# Adapter-TenX-Resistors.net
KiCad netlist of a schematic drawn in EAGLE
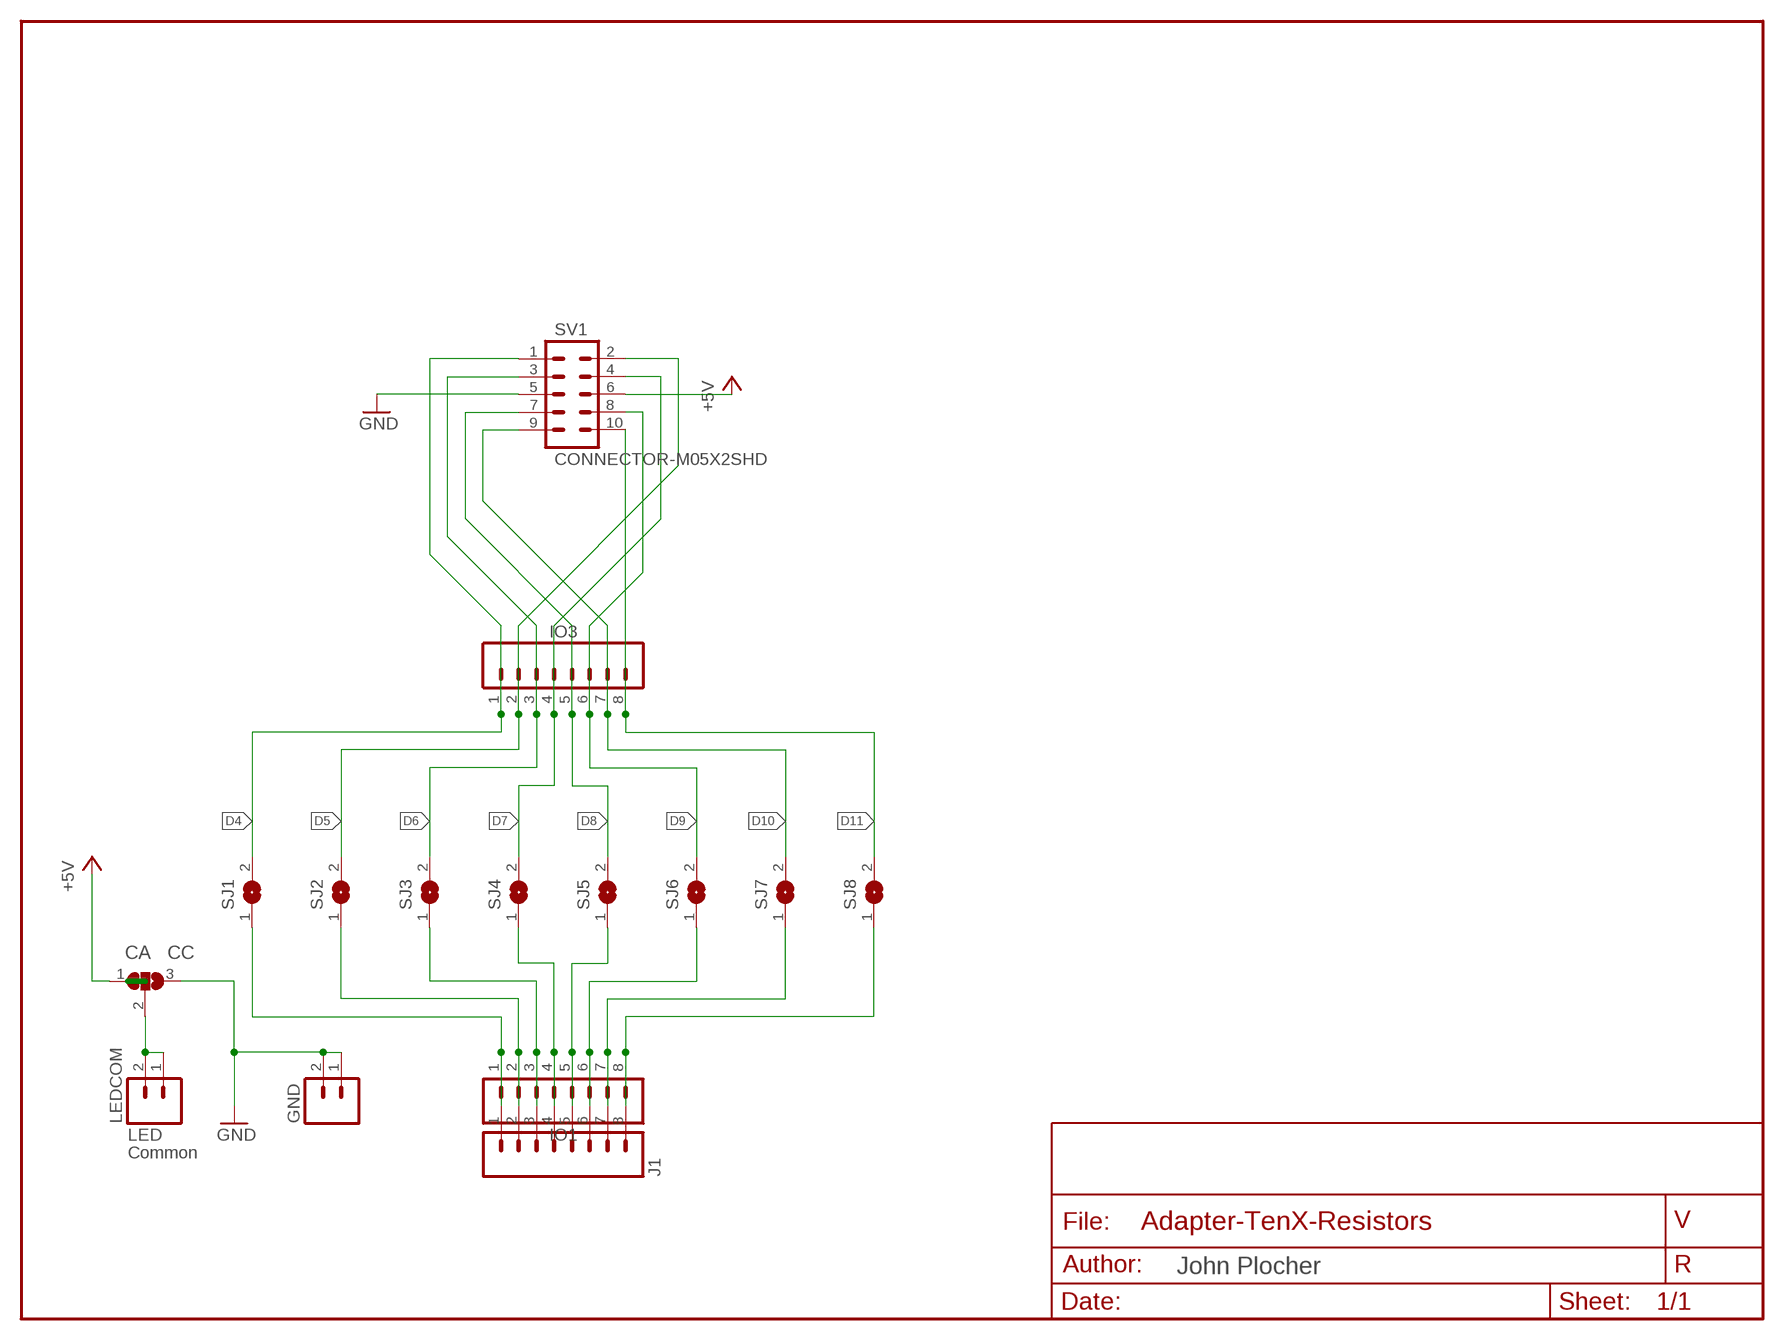
[diagram p0: schematic, sheet 1]

(export (version "E")
  (design (tool "Eeschema 10.0.6"))
  (components
    (comp (ref "GND")
      (value "M02POLAR_LOCK")
      (footprint "eagle-import:MOLEX-1X2_LOCK")
      (libsource (lib "eagle-import") (part "M02POLAR_LOCK"))
    )
    (comp (ref "IO1")
      (value "M081X08")
      (footprint "eagle-import:1X08")
      (libsource (lib "eagle-import") (part "M081X08"))
    )
    (comp (ref "IO3")
      (value "M081X08")
      (footprint "eagle-import:1X08")
      (libsource (lib "eagle-import") (part "M081X08"))
    )
    (comp (ref "J1")
      (value "CONNECTOR-M08LOCK_LONGPADS")
      (footprint "eagle-import:1X08_LOCK_LONGPADS")
      (libsource (lib "eagle-import") (part "CONNECTOR-M08LOCK_LONGPADS"))
    )
    (comp (ref "LEDCOM")
      (value "M02POLAR_LOCK")
      (footprint "eagle-import:MOLEX-1X2_LOCK")
      (libsource (lib "eagle-import") (part "M02POLAR_LOCK"))
    )
    (comp (ref "P1")
      (value "CA CC")
      (footprint "eagle-import:3P-SMD-2X4.8")
      (libsource (lib "eagle-import") (part "PAD-SOLDERJUMPER-2WAYT"))
    )
    (comp (ref "SJ1") (value "SJ") (footprint "eagle-import:SJ") (libsource (lib "eagle-import") (part "SJ")))
    (comp (ref "SJ2") (value "SJ") (footprint "eagle-import:SJ") (libsource (lib "eagle-import") (part "SJ")))
    (comp (ref "SJ3") (value "SJ") (footprint "eagle-import:SJ") (libsource (lib "eagle-import") (part "SJ")))
    (comp (ref "SJ4") (value "SJ") (footprint "eagle-import:SJ") (libsource (lib "eagle-import") (part "SJ")))
    (comp (ref "SJ5") (value "SJ") (footprint "eagle-import:SJ") (libsource (lib "eagle-import") (part "SJ")))
    (comp (ref "SJ6") (value "SJ") (footprint "eagle-import:SJ") (libsource (lib "eagle-import") (part "SJ")))
    (comp (ref "SJ7") (value "SJ") (footprint "eagle-import:SJ") (libsource (lib "eagle-import") (part "SJ")))
    (comp (ref "SJ8") (value "SJ") (footprint "eagle-import:SJ") (libsource (lib "eagle-import") (part "SJ")))
    (comp (ref "SV1")
      (value "CONNECTOR-M05X2SHD")
      (footprint "eagle-import:2X5-SHROUDED")
      (libsource (lib "eagle-import") (part "CONNECTOR-M05X2SHD"))
    )
  )
  (nets
    (net (code "1") (name "+5V") (class "Default")
      (node (ref "P1") (pin "1") (pinfunction "1_1") (pintype "passive"))
      (node (ref "SV1") (pin "6") (pinfunction "6_6") (pintype "passive"))
    )
    (net (code "2") (name "D4") (class "Default")
      (node (ref "IO3") (pin "1") (pinfunction "1_1") (pintype "passive"))
      (node (ref "SJ1") (pin "2") (pinfunction "2_2") (pintype "passive"))
      (node (ref "SV1") (pin "1") (pinfunction "1_1") (pintype "passive"))
    )
    (net (code "3") (name "D5") (class "Default")
      (node (ref "IO3") (pin "2") (pinfunction "2_2") (pintype "passive"))
      (node (ref "SJ2") (pin "2") (pinfunction "2_2") (pintype "passive"))
      (node (ref "SV1") (pin "2") (pinfunction "2_2") (pintype "passive"))
    )
    (net (code "4") (name "D6") (class "Default")
      (node (ref "IO3") (pin "3") (pinfunction "3_3") (pintype "passive"))
      (node (ref "SJ3") (pin "2") (pinfunction "2_2") (pintype "passive"))
      (node (ref "SV1") (pin "3") (pinfunction "3_3") (pintype "passive"))
    )
    (net (code "5") (name "D7") (class "Default")
      (node (ref "IO3") (pin "4") (pinfunction "4_4") (pintype "passive"))
      (node (ref "SJ4") (pin "2") (pinfunction "2_2") (pintype "passive"))
      (node (ref "SV1") (pin "4") (pinfunction "4_4") (pintype "passive"))
    )
    (net (code "6") (name "D8") (class "Default")
      (node (ref "IO3") (pin "5") (pinfunction "5_5") (pintype "passive"))
      (node (ref "SJ5") (pin "2") (pinfunction "2_2") (pintype "passive"))
      (node (ref "SV1") (pin "7") (pinfunction "7_7") (pintype "passive"))
    )
    (net (code "7") (name "D9") (class "Default")
      (node (ref "IO3") (pin "6") (pinfunction "6_6") (pintype "passive"))
      (node (ref "SJ6") (pin "2") (pinfunction "2_2") (pintype "passive"))
      (node (ref "SV1") (pin "8") (pinfunction "8_8") (pintype "passive"))
    )
    (net (code "8") (name "D10") (class "Default")
      (node (ref "IO3") (pin "7") (pinfunction "7_7") (pintype "passive"))
      (node (ref "SJ7") (pin "2") (pinfunction "2_2") (pintype "passive"))
      (node (ref "SV1") (pin "9") (pinfunction "9_9") (pintype "passive"))
    )
    (net (code "9") (name "D11") (class "Default")
      (node (ref "IO3") (pin "8") (pinfunction "8_8") (pintype "passive"))
      (node (ref "SJ8") (pin "2") (pinfunction "2_2") (pintype "passive"))
      (node (ref "SV1") (pin "10") (pinfunction "10_10") (pintype "passive"))
    )
    (net (code "10") (name "GND") (class "Default")
      (node (ref "GND") (pin "1") (pinfunction "1_1") (pintype "passive"))
      (node (ref "GND") (pin "2") (pinfunction "2_2") (pintype "passive"))
      (node (ref "P1") (pin "3") (pinfunction "3_3") (pintype "passive"))
      (node (ref "SV1") (pin "5") (pinfunction "5_5") (pintype "passive"))
    )
    (net (code "11") (name "Net-(IO1-Pad1)") (class "Default")
      (node (ref "IO1") (pin "1") (pinfunction "1_1") (pintype "passive"))
      (node (ref "J1") (pin "1") (pinfunction "1_1") (pintype "passive"))
      (node (ref "SJ1") (pin "1") (pinfunction "1_1") (pintype "passive"))
    )
    (net (code "12") (name "Net-(IO1-Pad2)") (class "Default")
      (node (ref "IO1") (pin "2") (pinfunction "2_2") (pintype "passive"))
      (node (ref "J1") (pin "2") (pinfunction "2_2") (pintype "passive"))
      (node (ref "SJ2") (pin "1") (pinfunction "1_1") (pintype "passive"))
    )
    (net (code "13") (name "Net-(IO1-Pad3)") (class "Default")
      (node (ref "IO1") (pin "3") (pinfunction "3_3") (pintype "passive"))
      (node (ref "J1") (pin "3") (pinfunction "3_3") (pintype "passive"))
      (node (ref "SJ3") (pin "1") (pinfunction "1_1") (pintype "passive"))
    )
    (net (code "14") (name "Net-(IO1-Pad4)") (class "Default")
      (node (ref "IO1") (pin "4") (pinfunction "4_4") (pintype "passive"))
      (node (ref "J1") (pin "4") (pinfunction "4_4") (pintype "passive"))
      (node (ref "SJ4") (pin "1") (pinfunction "1_1") (pintype "passive"))
    )
    (net (code "15") (name "Net-(IO1-Pad5)") (class "Default")
      (node (ref "IO1") (pin "5") (pinfunction "5_5") (pintype "passive"))
      (node (ref "J1") (pin "5") (pinfunction "5_5") (pintype "passive"))
      (node (ref "SJ5") (pin "1") (pinfunction "1_1") (pintype "passive"))
    )
    (net (code "16") (name "Net-(IO1-Pad6)") (class "Default")
      (node (ref "IO1") (pin "6") (pinfunction "6_6") (pintype "passive"))
      (node (ref "J1") (pin "6") (pinfunction "6_6") (pintype "passive"))
      (node (ref "SJ6") (pin "1") (pinfunction "1_1") (pintype "passive"))
    )
    (net (code "17") (name "Net-(IO1-Pad7)") (class "Default")
      (node (ref "IO1") (pin "7") (pinfunction "7_7") (pintype "passive"))
      (node (ref "J1") (pin "7") (pinfunction "7_7") (pintype "passive"))
      (node (ref "SJ7") (pin "1") (pinfunction "1_1") (pintype "passive"))
    )
    (net (code "18") (name "Net-(IO1-Pad8)") (class "Default")
      (node (ref "IO1") (pin "8") (pinfunction "8_8") (pintype "passive"))
      (node (ref "J1") (pin "8") (pinfunction "8_8") (pintype "passive"))
      (node (ref "SJ8") (pin "1") (pinfunction "1_1") (pintype "passive"))
    )
    (net (code "19") (name "Net-(LEDCOM-Pad1)") (class "Default")
      (node (ref "LEDCOM") (pin "1") (pinfunction "1_1") (pintype "passive"))
      (node (ref "LEDCOM") (pin "2") (pinfunction "2_2") (pintype "passive"))
      (node (ref "P1") (pin "2") (pinfunction "2_2") (pintype "passive"))
    )
  )
)
